# UTJ-1.net
KiCad netlist of a schematic drawn in EAGLE
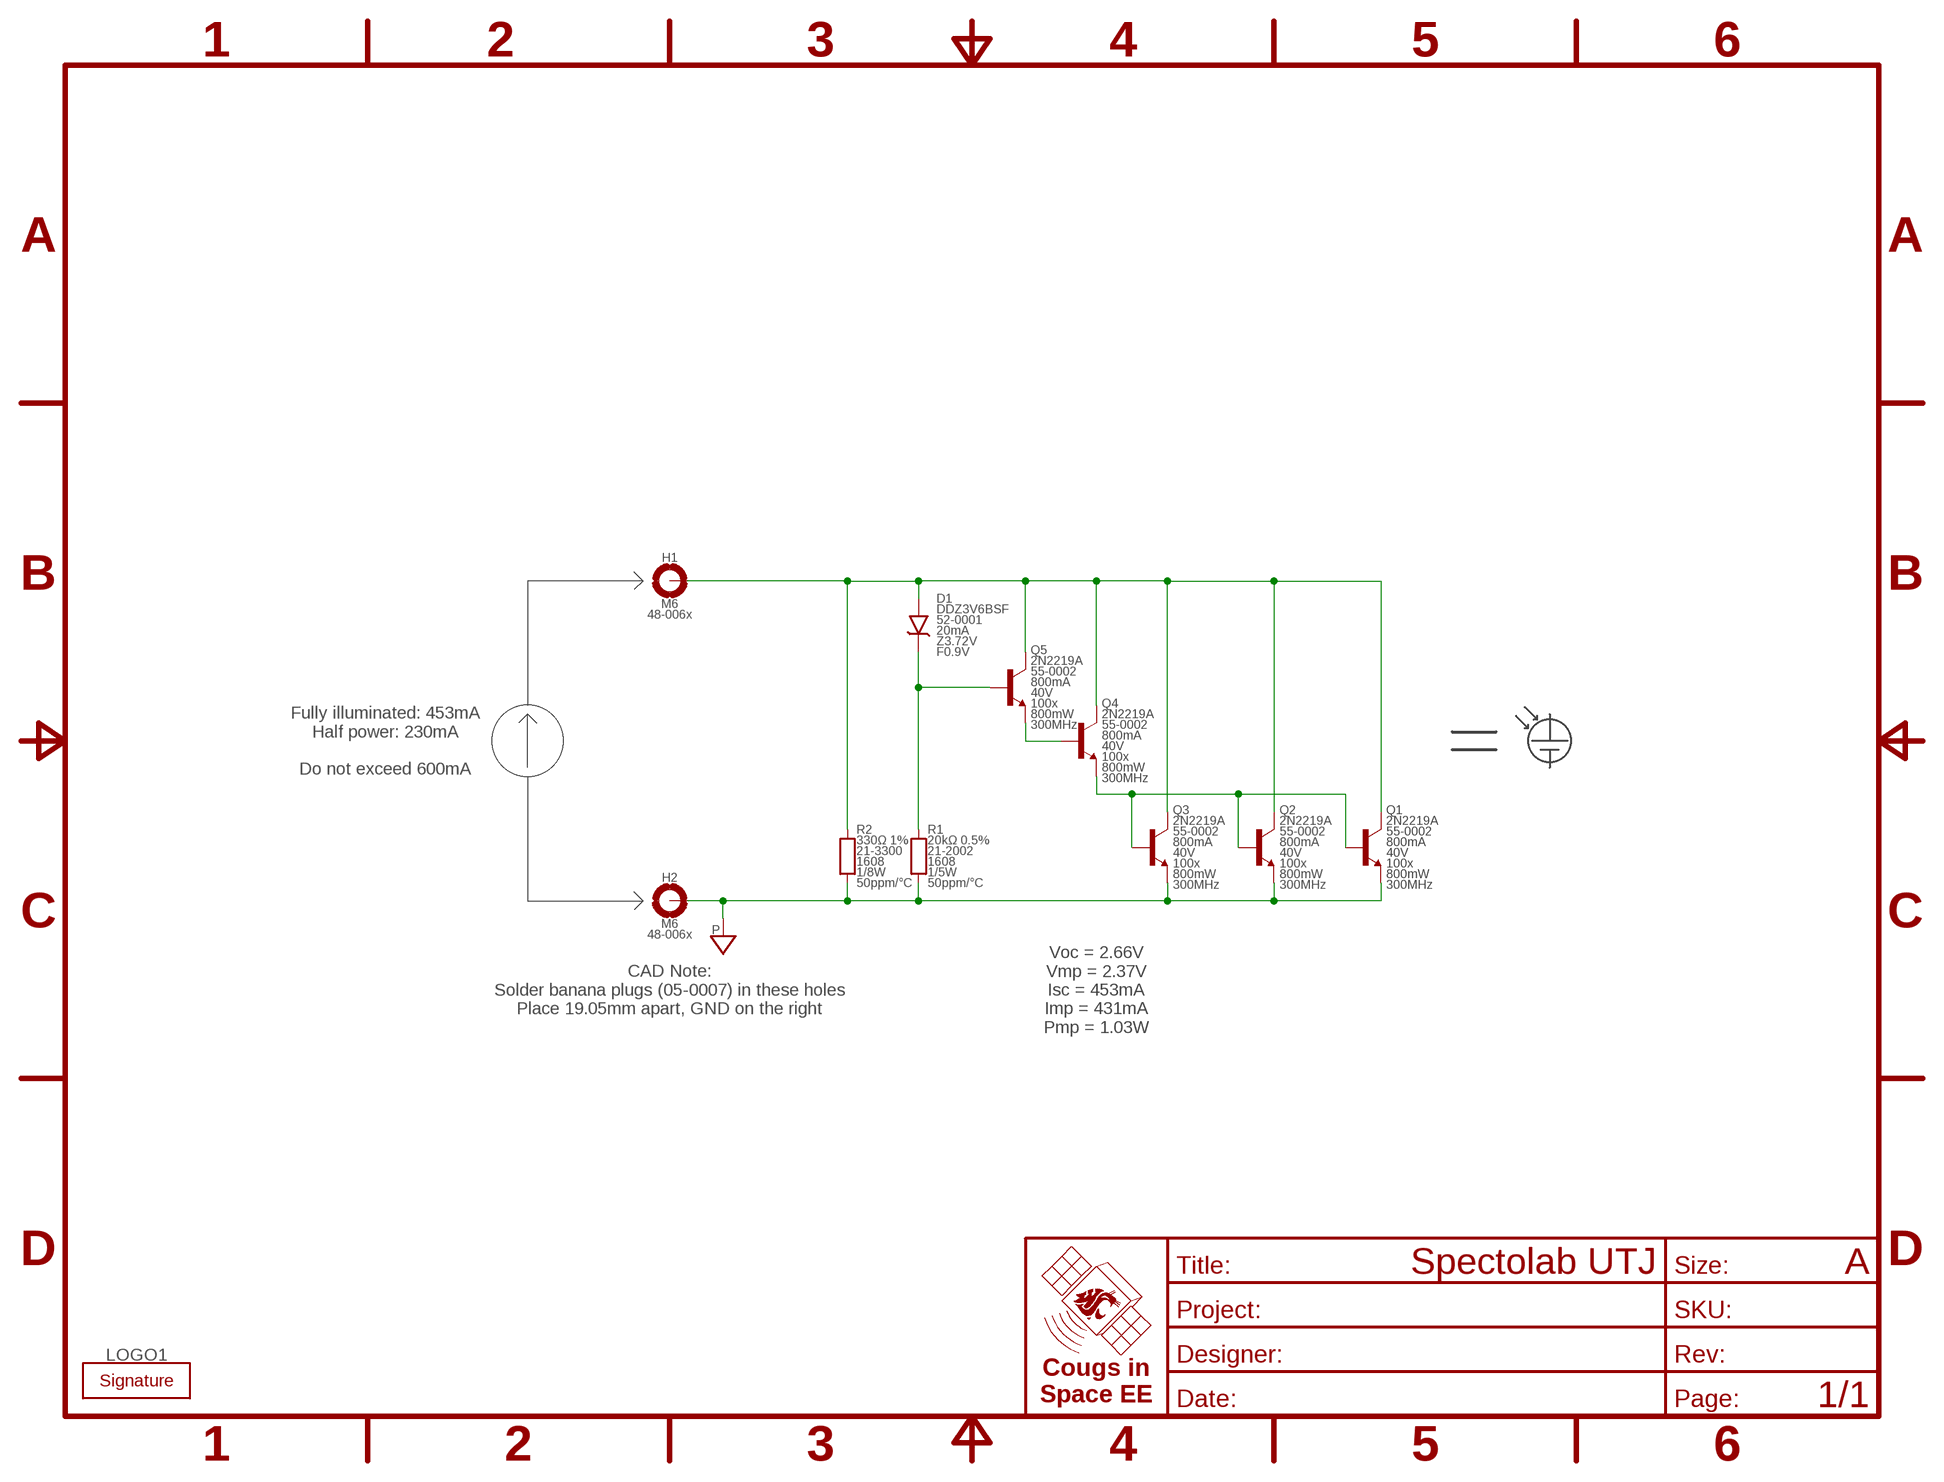
[diagram p0: schematic, sheet 1]

(export (version "E")
  (design (tool "Eeschema 10.0.6"))
  (components
    (comp (ref "D1")
      (value "DDZ3V6BSF")
      (footprint "eagle-import:SOD323F")
      (fields
        (field (name "CURRENT") "20mA")
        (field (name "SKU") "52-0001")
        (field (name "VF") "F0.9V")
        (field (name "VZ") "Z3.72V")
      )
      (libsource (lib "eagle-import") (part "DIODE-ZENER-V-SOD323F-DDZ3V6BSF"))
    )
    (comp (ref "H1")
      (value "M6")
      (footprint "eagle-import:MOUNTING_HOLE-6.6")
      (fields (field (name "SKU") "48-006x"))
      (libsource (lib "eagle-import") (part "MOUNTING_HOLE-6.6"))
    )
    (comp (ref "H2")
      (value "M6")
      (footprint "eagle-import:MOUNTING_HOLE-6.6")
      (fields (field (name "SKU") "48-006x"))
      (libsource (lib "eagle-import") (part "MOUNTING_HOLE-6.6"))
    )
    (comp (ref "LOGO1")
      (value "SIGNATUREBRADLEY")
      (footprint "eagle-import:SIGN-BRADLEY")
      (libsource (lib "eagle-import") (part "SIGNATUREBRADLEY"))
    )
    (comp (ref "Q1")
      (value "2N2219A")
      (footprint "eagle-import:TO-39")
      (fields
        (field (name "FREQ") "300MHz")
        (field (name "GAIN") "100x")
        (field (name "IMAX") "800mA")
        (field (name "POWER") "800mW")
        (field (name "SKU") "55-0002")
        (field (name "VMAX") "40V")
      )
      (libsource (lib "eagle-import") (part "BJT-NPN-TO-39-2N2219A"))
    )
    (comp (ref "Q2")
      (value "2N2219A")
      (footprint "eagle-import:TO-39")
      (fields
        (field (name "FREQ") "300MHz")
        (field (name "GAIN") "100x")
        (field (name "IMAX") "800mA")
        (field (name "POWER") "800mW")
        (field (name "SKU") "55-0002")
        (field (name "VMAX") "40V")
      )
      (libsource (lib "eagle-import") (part "BJT-NPN-TO-39-2N2219A"))
    )
    (comp (ref "Q3")
      (value "2N2219A")
      (footprint "eagle-import:TO-39")
      (fields
        (field (name "FREQ") "300MHz")
        (field (name "GAIN") "100x")
        (field (name "IMAX") "800mA")
        (field (name "POWER") "800mW")
        (field (name "SKU") "55-0002")
        (field (name "VMAX") "40V")
      )
      (libsource (lib "eagle-import") (part "BJT-NPN-TO-39-2N2219A"))
    )
    (comp (ref "Q4")
      (value "2N2219A")
      (footprint "eagle-import:TO-39")
      (fields
        (field (name "FREQ") "300MHz")
        (field (name "GAIN") "100x")
        (field (name "IMAX") "800mA")
        (field (name "POWER") "800mW")
        (field (name "SKU") "55-0002")
        (field (name "VMAX") "40V")
      )
      (libsource (lib "eagle-import") (part "BJT-NPN-TO-39-2N2219A"))
    )
    (comp (ref "Q5")
      (value "2N2219A")
      (footprint "eagle-import:TO-39")
      (fields
        (field (name "FREQ") "300MHz")
        (field (name "GAIN") "100x")
        (field (name "IMAX") "800mA")
        (field (name "POWER") "800mW")
        (field (name "SKU") "55-0002")
        (field (name "VMAX") "40V")
      )
      (libsource (lib "eagle-import") (part "BJT-NPN-TO-39-2N2219A"))
    )
    (comp (ref "R1")
      (value "20kΩ 0.5%")
      (footprint "eagle-import:1608")
      (fields
        (field (name "PACKAGE") "1608")
        (field (name "POWER") "1/5W")
        (field (name "SKU") "21-2002")
        (field (name "TEMP") "50ppm/°C")
      )
      (libsource (lib "eagle-import") (part "RES-V-1608-20K"))
    )
    (comp (ref "R2")
      (value "330Ω 1%")
      (footprint "eagle-import:1608")
      (fields
        (field (name "PACKAGE") "1608")
        (field (name "POWER") "1/8W")
        (field (name "SKU") "21-3300")
        (field (name "TEMP") "50ppm/°C")
      )
      (libsource (lib "eagle-import") (part "RES-V-1608-330R"))
    )
  )
  (nets
    (net (code "1") (name "Net-(Q1-B)") (class "Default")
      (node (ref "Q1") (pin "2") (pinfunction "B_2") (pintype "passive"))
      (node (ref "Q2") (pin "2") (pinfunction "B_2") (pintype "passive"))
      (node (ref "Q3") (pin "2") (pinfunction "B_2") (pintype "passive"))
      (node (ref "Q4") (pin "1") (pinfunction "E_1") (pintype "passive"))
    )
    (net (code "2") (name "Net-(Q1-C)") (class "Default")
      (node (ref "D1") (pin "A") (pinfunction "A_A") (pintype "passive"))
      (node (ref "H1") (pin "1") (pinfunction "MOUNT_1") (pintype "passive"))
      (node (ref "H1") (pin "V1") (pinfunction "MOUNT_V1") (pintype "passive"))
      (node (ref "H1") (pin "V10") (pinfunction "MOUNT_V10") (pintype "passive"))
      (node (ref "H1") (pin "V11") (pinfunction "MOUNT_V11") (pintype "passive"))
      (node (ref "H1") (pin "V12") (pinfunction "MOUNT_V12") (pintype "passive"))
      (node (ref "H1") (pin "V13") (pinfunction "MOUNT_V13") (pintype "passive"))
      (node (ref "H1") (pin "V14") (pinfunction "MOUNT_V14") (pintype "passive"))
      (node (ref "H1") (pin "V15") (pinfunction "MOUNT_V15") (pintype "passive"))
      (node (ref "H1") (pin "V16") (pinfunction "MOUNT_V16") (pintype "passive"))
      (node (ref "H1") (pin "V2") (pinfunction "MOUNT_V2") (pintype "passive"))
      (node (ref "H1") (pin "V3") (pinfunction "MOUNT_V3") (pintype "passive"))
      (node (ref "H1") (pin "V4") (pinfunction "MOUNT_V4") (pintype "passive"))
      (node (ref "H1") (pin "V5") (pinfunction "MOUNT_V5") (pintype "passive"))
      (node (ref "H1") (pin "V6") (pinfunction "MOUNT_V6") (pintype "passive"))
      (node (ref "H1") (pin "V7") (pinfunction "MOUNT_V7") (pintype "passive"))
      (node (ref "H1") (pin "V8") (pinfunction "MOUNT_V8") (pintype "passive"))
      (node (ref "H1") (pin "V9") (pinfunction "MOUNT_V9") (pintype "passive"))
      (node (ref "Q1") (pin "3") (pinfunction "C_3") (pintype "passive"))
      (node (ref "Q2") (pin "3") (pinfunction "C_3") (pintype "passive"))
      (node (ref "Q3") (pin "3") (pinfunction "C_3") (pintype "passive"))
      (node (ref "Q4") (pin "3") (pinfunction "C_3") (pintype "passive"))
      (node (ref "Q5") (pin "3") (pinfunction "C_3") (pintype "passive"))
      (node (ref "R2") (pin "2") (pinfunction "2_2") (pintype "passive"))
    )
    (net (code "3") (name "Net-(Q4-B)") (class "Default")
      (node (ref "Q4") (pin "2") (pinfunction "B_2") (pintype "passive"))
      (node (ref "Q5") (pin "1") (pinfunction "E_1") (pintype "passive"))
    )
    (net (code "4") (name "Net-(Q5-B)") (class "Default")
      (node (ref "D1") (pin "C") (pinfunction "C_C") (pintype "passive"))
      (node (ref "Q5") (pin "2") (pinfunction "B_2") (pintype "passive"))
      (node (ref "R1") (pin "2") (pinfunction "2_2") (pintype "passive"))
    )
    (net (code "5") (name "PGND") (class "Default")
      (node (ref "H2") (pin "1") (pinfunction "MOUNT_1") (pintype "passive"))
      (node (ref "H2") (pin "V1") (pinfunction "MOUNT_V1") (pintype "passive"))
      (node (ref "H2") (pin "V10") (pinfunction "MOUNT_V10") (pintype "passive"))
      (node (ref "H2") (pin "V11") (pinfunction "MOUNT_V11") (pintype "passive"))
      (node (ref "H2") (pin "V12") (pinfunction "MOUNT_V12") (pintype "passive"))
      (node (ref "H2") (pin "V13") (pinfunction "MOUNT_V13") (pintype "passive"))
      (node (ref "H2") (pin "V14") (pinfunction "MOUNT_V14") (pintype "passive"))
      (node (ref "H2") (pin "V15") (pinfunction "MOUNT_V15") (pintype "passive"))
      (node (ref "H2") (pin "V16") (pinfunction "MOUNT_V16") (pintype "passive"))
      (node (ref "H2") (pin "V2") (pinfunction "MOUNT_V2") (pintype "passive"))
      (node (ref "H2") (pin "V3") (pinfunction "MOUNT_V3") (pintype "passive"))
      (node (ref "H2") (pin "V4") (pinfunction "MOUNT_V4") (pintype "passive"))
      (node (ref "H2") (pin "V5") (pinfunction "MOUNT_V5") (pintype "passive"))
      (node (ref "H2") (pin "V6") (pinfunction "MOUNT_V6") (pintype "passive"))
      (node (ref "H2") (pin "V7") (pinfunction "MOUNT_V7") (pintype "passive"))
      (node (ref "H2") (pin "V8") (pinfunction "MOUNT_V8") (pintype "passive"))
      (node (ref "H2") (pin "V9") (pinfunction "MOUNT_V9") (pintype "passive"))
      (node (ref "Q1") (pin "1") (pinfunction "E_1") (pintype "passive"))
      (node (ref "Q2") (pin "1") (pinfunction "E_1") (pintype "passive"))
      (node (ref "Q3") (pin "1") (pinfunction "E_1") (pintype "passive"))
      (node (ref "R1") (pin "1") (pinfunction "1_1") (pintype "passive"))
      (node (ref "R2") (pin "1") (pinfunction "1_1") (pintype "passive"))
    )
  )
)
